# RoboDrum_Final.net
KiCad netlist of a schematic drawn in EAGLE
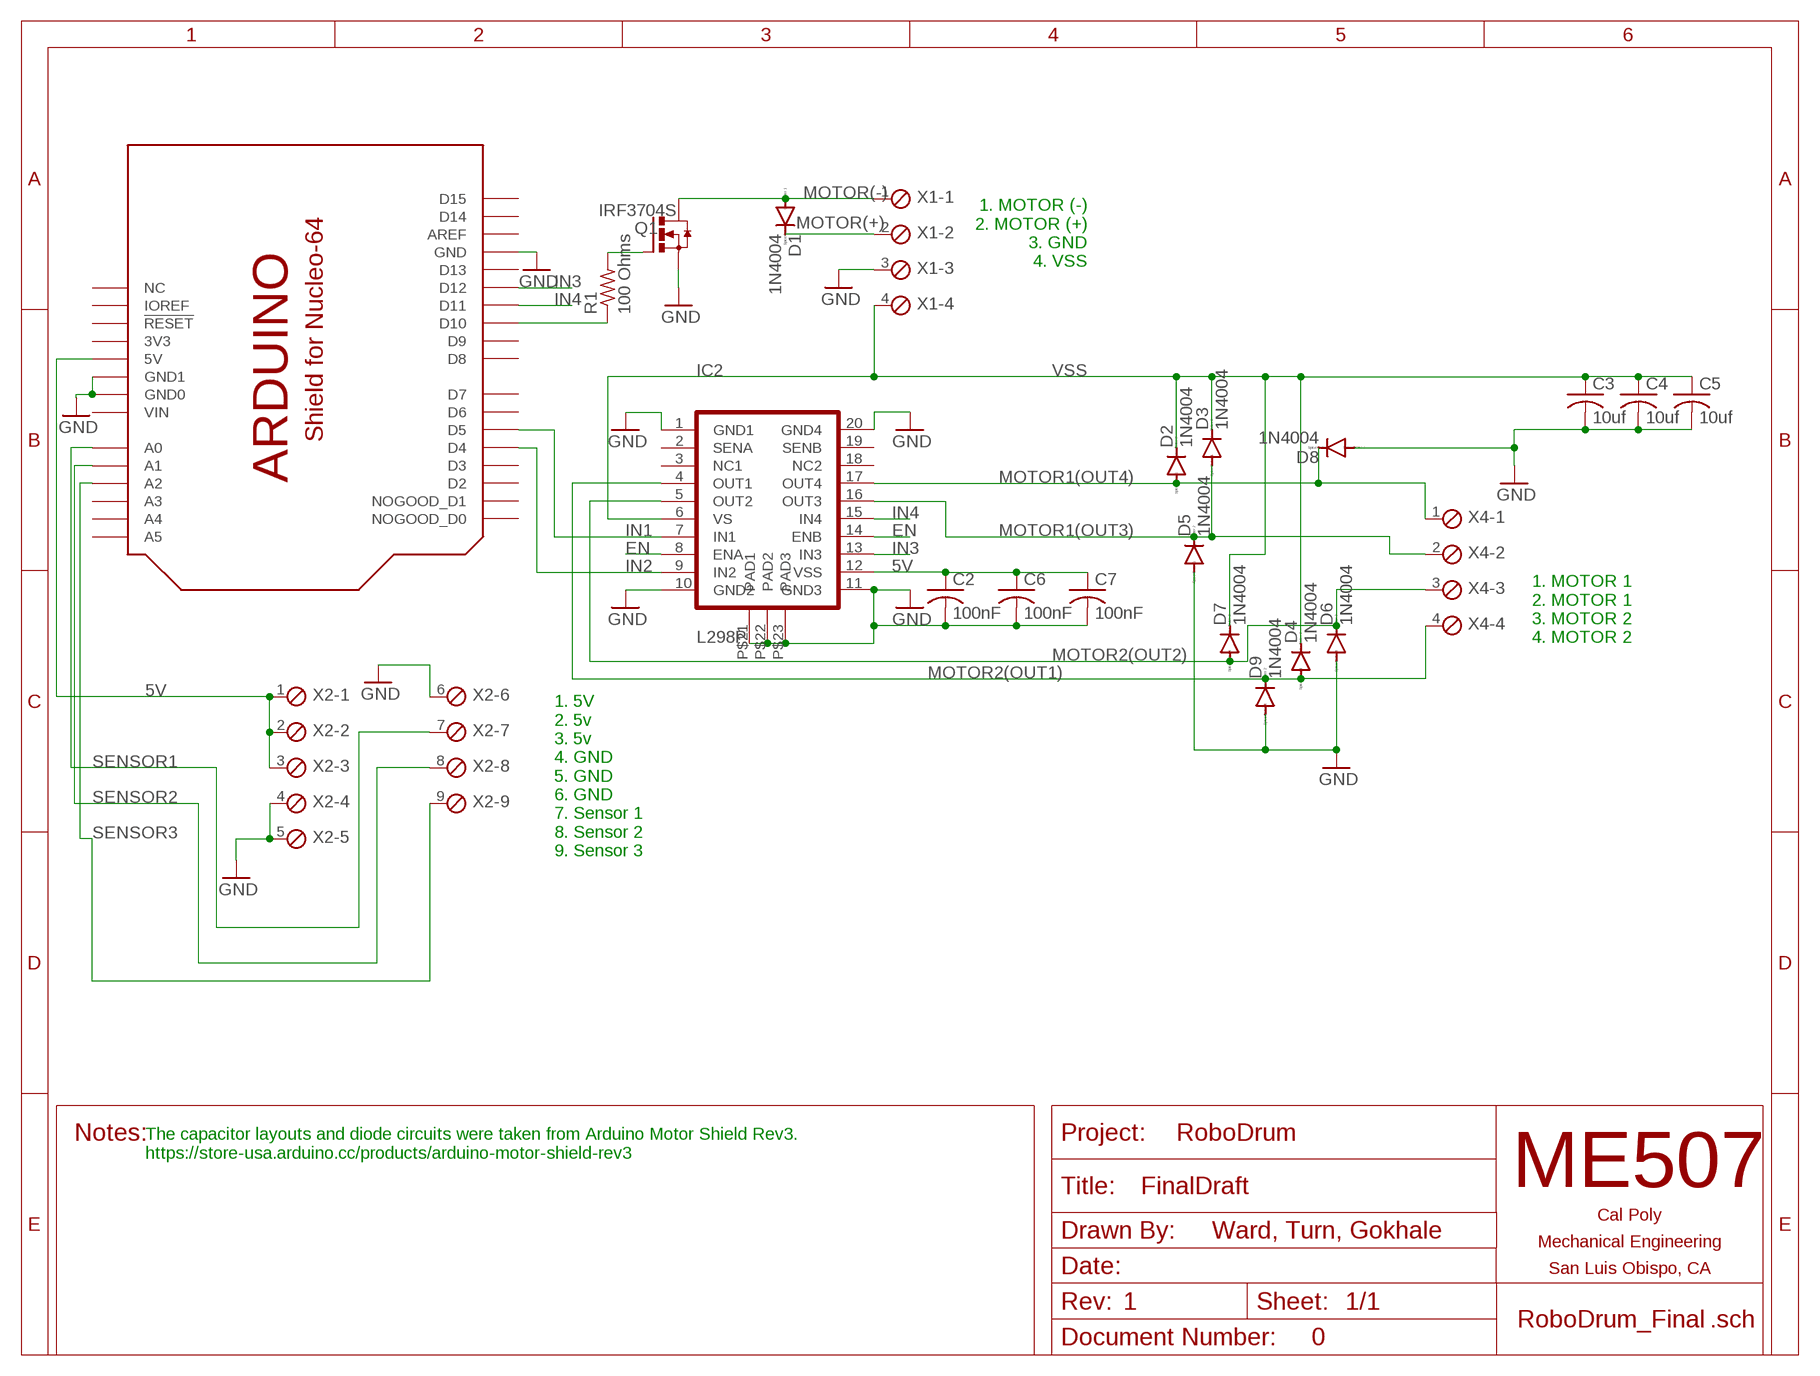
[diagram p0: schematic, sheet 1]

(export (version "E")
  (design (tool "Eeschema 10.0.6"))
  (components
    (comp (ref "C2")
      (value "100nF")
      (footprint "eagle-import:C0805")
      (libsource (lib "eagle-import") (part "C-USC0805"))
    )
    (comp (ref "C3")
      (value "10uf")
      (footprint "eagle-import:C1206")
      (libsource (lib "eagle-import") (part "C-USC1206"))
    )
    (comp (ref "C4")
      (value "10uf")
      (footprint "eagle-import:C1206")
      (libsource (lib "eagle-import") (part "C-USC1206"))
    )
    (comp (ref "C5")
      (value "10uf")
      (footprint "eagle-import:C1206")
      (libsource (lib "eagle-import") (part "C-USC1206"))
    )
    (comp (ref "C6")
      (value "100nF")
      (footprint "eagle-import:C0805")
      (libsource (lib "eagle-import") (part "C-USC0805"))
    )
    (comp (ref "C7")
      (value "100nF")
      (footprint "eagle-import:C0805")
      (libsource (lib "eagle-import") (part "C-USC0805"))
    )
    (comp (ref "D1")
      (value "1N4004")
      (footprint "eagle-import:DO41-10")
      (libsource (lib "eagle-import") (part "1N4004"))
    )
    (comp (ref "D2")
      (value "1N4004")
      (footprint "eagle-import:DO41-10")
      (libsource (lib "eagle-import") (part "1N4004"))
    )
    (comp (ref "D3")
      (value "1N4004")
      (footprint "eagle-import:DO41-10")
      (libsource (lib "eagle-import") (part "1N4004"))
    )
    (comp (ref "D4")
      (value "1N4004")
      (footprint "eagle-import:DO41-10")
      (libsource (lib "eagle-import") (part "1N4004"))
    )
    (comp (ref "D5")
      (value "1N4004")
      (footprint "eagle-import:DO41-10")
      (libsource (lib "eagle-import") (part "1N4004"))
    )
    (comp (ref "D6")
      (value "1N4004")
      (footprint "eagle-import:DO41-10")
      (libsource (lib "eagle-import") (part "1N4004"))
    )
    (comp (ref "D7")
      (value "1N4004")
      (footprint "eagle-import:DO41-10")
      (libsource (lib "eagle-import") (part "1N4004"))
    )
    (comp (ref "D8")
      (value "1N4004")
      (footprint "eagle-import:DO41-10")
      (libsource (lib "eagle-import") (part "1N4004"))
    )
    (comp (ref "D9")
      (value "1N4004")
      (footprint "eagle-import:DO41-10")
      (libsource (lib "eagle-import") (part "1N4004"))
    )
    (comp (ref "IC2")
      (value "L298P")
      (footprint "eagle-import:POWER-SO20")
      (libsource (lib "eagle-import") (part "L298P"))
    )
    (comp (ref "Q1")
      (value "IRF3704S")
      (footprint "eagle-import:D2PACK")
      (libsource (lib "eagle-import") (part "IRF3704S"))
    )
    (comp (ref "R1")
      (value "100 Ohms")
      (footprint "eagle-import:M0805")
      (libsource (lib "eagle-import") (part "R-US_M0805"))
    )
    (comp (ref "U$1")
      (value "SHIELD_FOR_NUCLE0_64_STANDARD")
      (footprint "eagle-import:SHIELD_FOR_NUCLEO_64_STD")
      (libsource (lib "eagle-import") (part "SHIELD_FOR_NUCLE0_64_STANDARD"))
    )
    (comp (ref "X1")
      (value "SCREWTERM_4P_381")
      (footprint "eagle-import:4POL381")
      (libsource (lib "eagle-import") (part "SCREWTERM_4P_381"))
    )
    (comp (ref "X2")
      (value "SCREWTERM_9P_254")
      (footprint "eagle-import:9POL254")
      (libsource (lib "eagle-import") (part "SCREWTERM_9P_254"))
    )
    (comp (ref "X4")
      (value "SCREWTERM_4P_254")
      (footprint "eagle-import:4POL254")
      (libsource (lib "eagle-import") (part "SCREWTERM_4P_254"))
    )
  )
  (nets
    (net (code "1") (name "/3V3") (class "Default")
      (node (ref "U$1") (pin "3V") (pinfunction "3V3_3V") (pintype "power_in"))
    )
    (net (code "2") (name "/5V") (class "Default")
      (node (ref "C2") (pin "1") (pinfunction "1_1") (pintype "passive"))
      (node (ref "C6") (pin "1") (pinfunction "1_1") (pintype "passive"))
      (node (ref "C7") (pin "1") (pinfunction "1_1") (pintype "passive"))
      (node (ref "IC2") (pin "P$12") (pinfunction "VSS_P$12") (pintype "power_in"))
      (node (ref "U$1") (pin "5V") (pinfunction "5V_5V") (pintype "power_in"))
      (node (ref "X2") (pin "1") (pinfunction "1_1") (pintype "passive"))
      (node (ref "X2") (pin "2") (pinfunction "1_2") (pintype "passive"))
      (node (ref "X2") (pin "3") (pinfunction "1_3") (pintype "passive"))
    )
    (net (code "3") (name "/EN") (class "Default")
      (node (ref "IC2") (pin "P$14") (pinfunction "ENB_P$14") (pintype "input"))
      (node (ref "IC2") (pin "P$8") (pinfunction "ENA_P$8") (pintype "input"))
    )
    (net (code "4") (name "/IN1") (class "Default")
      (node (ref "IC2") (pin "P$7") (pinfunction "IN1_P$7") (pintype "input"))
      (node (ref "U$1") (pin "D5") (pinfunction "D5_D5") (pintype "bidirectional"))
    )
    (net (code "5") (name "/IN2") (class "Default")
      (node (ref "IC2") (pin "P$9") (pinfunction "IN2_P$9") (pintype "input"))
      (node (ref "U$1") (pin "D4") (pinfunction "D4_D4") (pintype "bidirectional"))
    )
    (net (code "6") (name "/IN3") (class "Default")
      (node (ref "IC2") (pin "P$13") (pinfunction "IN3_P$13") (pintype "input"))
      (node (ref "U$1") (pin "D12") (pinfunction "D12_D12") (pintype "bidirectional"))
    )
    (net (code "7") (name "/IN4") (class "Default")
      (node (ref "IC2") (pin "P$15") (pinfunction "IN4_P$15") (pintype "input"))
      (node (ref "U$1") (pin "D11") (pinfunction "D11_D11") (pintype "bidirectional"))
    )
    (net (code "8") (name "/MOTOR(+)") (class "Default")
      (node (ref "D1") (pin "C") (pinfunction "C_C") (pintype "passive"))
      (node (ref "X1") (pin "2") (pinfunction "1_2") (pintype "passive"))
    )
    (net (code "9") (name "/MOTOR(-)") (class "Default")
      (node (ref "D1") (pin "A") (pinfunction "A_A") (pintype "passive"))
      (node (ref "Q1") (pin "2") (pinfunction "D_2") (pintype "passive"))
      (node (ref "X1") (pin "1") (pinfunction "1_1") (pintype "passive"))
    )
    (net (code "10") (name "/MOTOR1(OUT3)") (class "Default")
      (node (ref "D3") (pin "A") (pinfunction "A_A") (pintype "passive"))
      (node (ref "D5") (pin "C") (pinfunction "C_C") (pintype "passive"))
      (node (ref "IC2") (pin "P$16") (pinfunction "OUT3_P$16") (pintype "output"))
      (node (ref "X4") (pin "2") (pinfunction "1_2") (pintype "passive"))
    )
    (net (code "11") (name "/MOTOR1(OUT4)") (class "Default")
      (node (ref "D2") (pin "A") (pinfunction "A_A") (pintype "passive"))
      (node (ref "D8") (pin "C") (pinfunction "C_C") (pintype "passive"))
      (node (ref "IC2") (pin "P$17") (pinfunction "OUT4_P$17") (pintype "output"))
      (node (ref "X4") (pin "1") (pinfunction "1_1") (pintype "passive"))
    )
    (net (code "12") (name "/MOTOR2(OUT1)") (class "Default")
      (node (ref "D4") (pin "A") (pinfunction "A_A") (pintype "passive"))
      (node (ref "D9") (pin "C") (pinfunction "C_C") (pintype "passive"))
      (node (ref "IC2") (pin "P$4") (pinfunction "OUT1_P$4") (pintype "output"))
      (node (ref "X4") (pin "4") (pinfunction "1_4") (pintype "passive"))
    )
    (net (code "13") (name "/MOTOR2(OUT2)") (class "Default")
      (node (ref "D6") (pin "C") (pinfunction "C_C") (pintype "passive"))
      (node (ref "D7") (pin "A") (pinfunction "A_A") (pintype "passive"))
      (node (ref "IC2") (pin "P$5") (pinfunction "OUT2_P$5") (pintype "output"))
      (node (ref "X4") (pin "3") (pinfunction "1_3") (pintype "passive"))
    )
    (net (code "14") (name "/SENSOR1") (class "Default")
      (node (ref "U$1") (pin "A2") (pinfunction "A2_A2") (pintype "bidirectional"))
      (node (ref "X2") (pin "9") (pinfunction "1_9") (pintype "passive"))
    )
    (net (code "15") (name "/SENSOR2") (class "Default")
      (node (ref "U$1") (pin "A1") (pinfunction "A1_A1") (pintype "bidirectional"))
      (node (ref "X2") (pin "8") (pinfunction "1_8") (pintype "passive"))
    )
    (net (code "16") (name "/SENSOR3") (class "Default")
      (node (ref "U$1") (pin "A0") (pinfunction "A0_A0") (pintype "bidirectional"))
      (node (ref "X2") (pin "7") (pinfunction "1_7") (pintype "passive"))
    )
    (net (code "17") (name "/VIN") (class "Default")
      (node (ref "U$1") (pin "VIN") (pinfunction "VIN_VIN") (pintype "power_in"))
    )
    (net (code "18") (name "/VSS") (class "Default")
      (node (ref "C3") (pin "1") (pinfunction "1_1") (pintype "passive"))
      (node (ref "C4") (pin "1") (pinfunction "1_1") (pintype "passive"))
      (node (ref "C5") (pin "1") (pinfunction "1_1") (pintype "passive"))
      (node (ref "D2") (pin "C") (pinfunction "C_C") (pintype "passive"))
      (node (ref "D3") (pin "C") (pinfunction "C_C") (pintype "passive"))
      (node (ref "D4") (pin "C") (pinfunction "C_C") (pintype "passive"))
      (node (ref "D7") (pin "C") (pinfunction "C_C") (pintype "passive"))
      (node (ref "IC2") (pin "P$6") (pinfunction "VS_P$6") (pintype "power_in"))
      (node (ref "X1") (pin "4") (pinfunction "1_4") (pintype "passive"))
    )
    (net (code "19") (name "GND") (class "Default")
      (node (ref "C2") (pin "2") (pinfunction "2_2") (pintype "passive"))
      (node (ref "C3") (pin "2") (pinfunction "2_2") (pintype "passive"))
      (node (ref "C4") (pin "2") (pinfunction "2_2") (pintype "passive"))
      (node (ref "C5") (pin "2") (pinfunction "2_2") (pintype "passive"))
      (node (ref "C6") (pin "2") (pinfunction "2_2") (pintype "passive"))
      (node (ref "C7") (pin "2") (pinfunction "2_2") (pintype "passive"))
      (node (ref "D5") (pin "A") (pinfunction "A_A") (pintype "passive"))
      (node (ref "D6") (pin "A") (pinfunction "A_A") (pintype "passive"))
      (node (ref "D8") (pin "A") (pinfunction "A_A") (pintype "passive"))
      (node (ref "D9") (pin "A") (pinfunction "A_A") (pintype "passive"))
      (node (ref "IC2") (pin "P$1") (pinfunction "GND1_P$1") (pintype "power_in"))
      (node (ref "IC2") (pin "P$10") (pinfunction "GND2_P$10") (pintype "power_in"))
      (node (ref "IC2") (pin "P$11") (pinfunction "GND3_P$11") (pintype "power_in"))
      (node (ref "IC2") (pin "P$20") (pinfunction "GND4_P$20") (pintype "power_in"))
      (node (ref "IC2") (pin "P$21") (pinfunction "PAD1_P$21") (pintype "passive"))
      (node (ref "IC2") (pin "P$22") (pinfunction "PAD2_P$22") (pintype "passive"))
      (node (ref "IC2") (pin "P$23") (pinfunction "PAD3_P$23") (pintype "passive"))
      (node (ref "Q1") (pin "3") (pinfunction "S_3") (pintype "passive"))
      (node (ref "U$1") (pin "GND") (pinfunction "GND_GND") (pintype "power_in"))
      (node (ref "U$1") (pin "GND1") (pinfunction "GND0_GND1") (pintype "power_in"))
      (node (ref "U$1") (pin "GND2") (pinfunction "GND1_GND2") (pintype "power_in"))
      (node (ref "X1") (pin "3") (pinfunction "1_3") (pintype "passive"))
      (node (ref "X2") (pin "4") (pinfunction "1_4") (pintype "passive"))
      (node (ref "X2") (pin "5") (pinfunction "1_5") (pintype "passive"))
      (node (ref "X2") (pin "6") (pinfunction "1_6") (pintype "passive"))
    )
    (net (code "20") (name "Net-(Q1-G)") (class "Default")
      (node (ref "Q1") (pin "1") (pinfunction "G_1") (pintype "passive"))
      (node (ref "R1") (pin "2") (pinfunction "2_2") (pintype "passive"))
    )
    (net (code "21") (name "Net-(R1-Pad1)") (class "Default")
      (node (ref "R1") (pin "1") (pinfunction "1_1") (pintype "passive"))
      (node (ref "U$1") (pin "D10") (pinfunction "D10_D10") (pintype "bidirectional"))
    )
    (net (code "22") (name "unconnected-(IC2-NC1-PadP$3)") (class "Default")
      (node (ref "IC2") (pin "P$3") (pinfunction "NC1_P$3") (pintype "no_connect"))
    )
    (net (code "23") (name "unconnected-(IC2-NC2-PadP$18)") (class "Default")
      (node (ref "IC2") (pin "P$18") (pinfunction "NC2_P$18") (pintype "no_connect"))
    )
    (net (code "24") (name "unconnected-(IC2-SENA-PadP$2)") (class "Default")
      (node (ref "IC2") (pin "P$2") (pinfunction "SENA_P$2") (pintype "input"))
    )
    (net (code "25") (name "unconnected-(IC2-SENB-PadP$19)") (class "Default")
      (node (ref "IC2") (pin "P$19") (pinfunction "SENB_P$19") (pintype "input"))
    )
    (net (code "26") (name "unconnected-(U$1-NOGOOD_D0-PadD0)") (class "Default")
      (node (ref "U$1") (pin "D0") (pinfunction "NOGOOD_D0_D0") (pintype "no_connect"))
    )
    (net (code "27") (name "unconnected-(U$1-NOGOOD_D1-PadD1)") (class "Default")
      (node (ref "U$1") (pin "D1") (pinfunction "NOGOOD_D1_D1") (pintype "no_connect"))
    )
    (net (code "28") (name "unconnected-(U$1-PadA3)") (class "Default")
      (node (ref "U$1") (pin "A3") (pinfunction "A3_A3") (pintype "bidirectional"))
    )
    (net (code "29") (name "unconnected-(U$1-PadA4)") (class "Default")
      (node (ref "U$1") (pin "A4") (pinfunction "A4_A4") (pintype "bidirectional"))
    )
    (net (code "30") (name "unconnected-(U$1-PadA5)") (class "Default")
      (node (ref "U$1") (pin "A5") (pinfunction "A5_A5") (pintype "bidirectional"))
    )
    (net (code "31") (name "unconnected-(U$1-PadAREF)") (class "Default")
      (node (ref "U$1") (pin "AREF") (pinfunction "AREF_AREF") (pintype "bidirectional"))
    )
    (net (code "32") (name "unconnected-(U$1-PadD2)") (class "Default")
      (node (ref "U$1") (pin "D2") (pinfunction "D2_D2") (pintype "bidirectional"))
    )
    (net (code "33") (name "unconnected-(U$1-PadD3)") (class "Default")
      (node (ref "U$1") (pin "D3") (pinfunction "D3_D3") (pintype "bidirectional"))
    )
    (net (code "34") (name "unconnected-(U$1-PadD6)") (class "Default")
      (node (ref "U$1") (pin "D6") (pinfunction "D6_D6") (pintype "bidirectional"))
    )
    (net (code "35") (name "unconnected-(U$1-PadD7)") (class "Default")
      (node (ref "U$1") (pin "D7") (pinfunction "D7_D7") (pintype "bidirectional"))
    )
    (net (code "36") (name "unconnected-(U$1-PadD8)") (class "Default")
      (node (ref "U$1") (pin "D8") (pinfunction "D8_D8") (pintype "bidirectional"))
    )
    (net (code "37") (name "unconnected-(U$1-PadD9)") (class "Default")
      (node (ref "U$1") (pin "D9") (pinfunction "D9_D9") (pintype "bidirectional"))
    )
    (net (code "38") (name "unconnected-(U$1-PadD13)") (class "Default")
      (node (ref "U$1") (pin "D13") (pinfunction "D13_D13") (pintype "bidirectional"))
    )
    (net (code "39") (name "unconnected-(U$1-PadD14)") (class "Default")
      (node (ref "U$1") (pin "D14") (pinfunction "D14_D14") (pintype "bidirectional"))
    )
    (net (code "40") (name "unconnected-(U$1-PadD15)") (class "Default")
      (node (ref "U$1") (pin "D15") (pinfunction "D15_D15") (pintype "bidirectional"))
    )
    (net (code "41") (name "unconnected-(U$1-PadIOREF)") (class "Default")
      (node (ref "U$1") (pin "IOREF") (pinfunction "IOREF_IOREF") (pintype "bidirectional"))
    )
    (net (code "42") (name "unconnected-(U$1-PadNC)") (class "Default")
      (node (ref "U$1") (pin "NC") (pinfunction "NC_NC") (pintype "no_connect"))
    )
    (net (code "43") (name "unconnected-(U$1-~{RESET}-PadNRST)") (class "Default")
      (node (ref "U$1") (pin "NRST") (pinfunction "~{RESET}_NRST") (pintype "input"))
    )
  )
)
